# weblight_developer.net
KiCad netlist of a schematic drawn in EAGLE
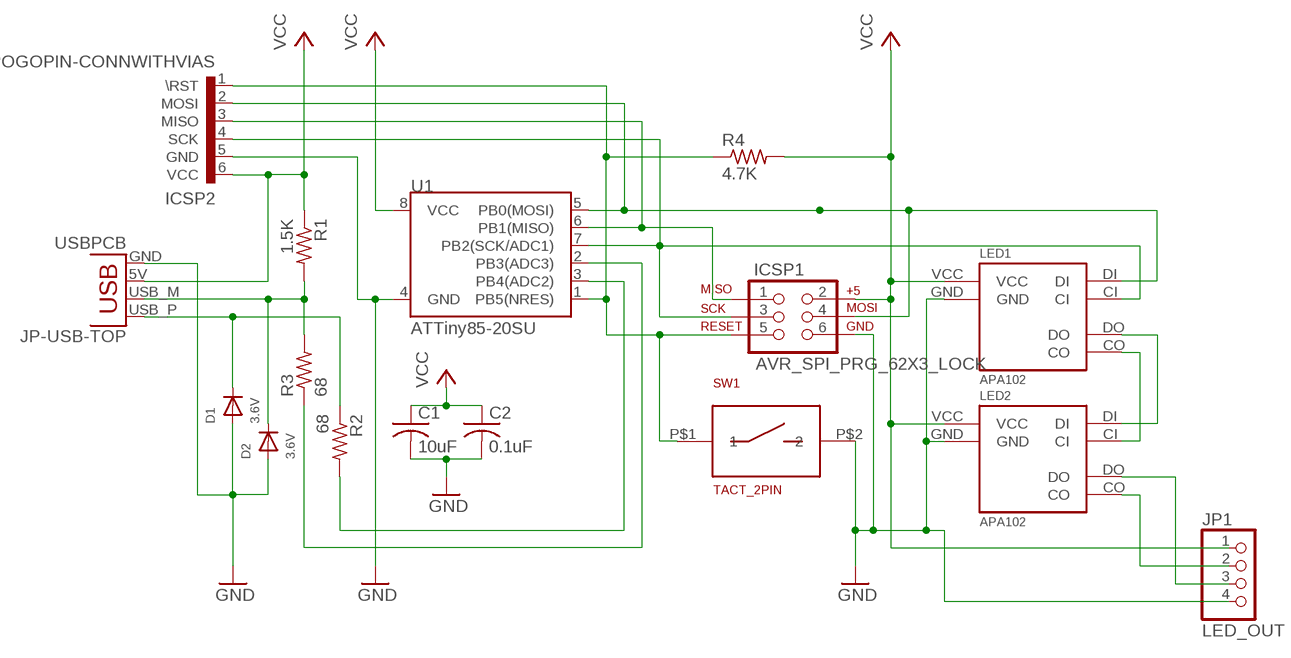
[diagram p0: schematic, sheet 1]

(export (version "E")
  (design (tool "Eeschema 10.0.6"))
  (components
    (comp (ref "C1")
      (value "10uF")
      (footprint "eagle-import:C0805")
      (libsource (lib "eagle-import") (part "C-USC0805"))
    )
    (comp (ref "C2")
      (value "0.1uF")
      (footprint "eagle-import:C0805")
      (libsource (lib "eagle-import") (part "C-USC0805"))
    )
    (comp (ref "D1")
      (value "3.6V")
      (footprint "eagle-import:SOD-323")
      (libsource (lib "eagle-import") (part "DIODESOD-323"))
    )
    (comp (ref "D2")
      (value "3.6V")
      (footprint "eagle-import:SOD-323")
      (libsource (lib "eagle-import") (part "DIODESOD-323"))
    )
    (comp (ref "ICSP1")
      (value "AVR_SPI_PRG_62X3_LOCK")
      (footprint "eagle-import:2X3_LOCK")
      (libsource (lib "eagle-import") (part "AVR_SPI_PRG_62X3_LOCK"))
    )
    (comp (ref "ICSP2")
      (value "POGOPIN-CONNWITHVIAS")
      (footprint "eagle-import:POGOPROG-CONN-0H")
      (libsource (lib "eagle-import") (part "POGOPIN-CONNWITHVIAS"))
    )
    (comp (ref "JP-USB-TOP")
      (value "USBPCB")
      (footprint "eagle-import:USB-A-PCB")
      (libsource (lib "eagle-import") (part "USBPCB"))
    )
    (comp (ref "JP1")
      (value "LED_OUT")
      (footprint "eagle-import:1X04_ROUND")
      (libsource (lib "eagle-import") (part "HEADER-1X4ROUND"))
    )
    (comp (ref "LED1")
      (value "APA102")
      (footprint "eagle-import:APA102")
      (libsource (lib "eagle-import") (part "APA102"))
    )
    (comp (ref "LED2")
      (value "APA102")
      (footprint "eagle-import:APA102")
      (libsource (lib "eagle-import") (part "APA102"))
    )
    (comp (ref "R1")
      (value "1.5K")
      (footprint "eagle-import:R0805")
      (libsource (lib "eagle-import") (part "R-US_R0805"))
    )
    (comp (ref "R2")
      (value "68")
      (footprint "eagle-import:R0805")
      (libsource (lib "eagle-import") (part "R-US_R0805"))
    )
    (comp (ref "R3")
      (value "68")
      (footprint "eagle-import:R0805")
      (libsource (lib "eagle-import") (part "R-US_R0805"))
    )
    (comp (ref "R4")
      (value "4.7K")
      (footprint "eagle-import:R0805")
      (libsource (lib "eagle-import") (part "R-US_R0805"))
    )
    (comp (ref "SW1")
      (value "TACT_2PIN")
      (footprint "eagle-import:TD-85XU")
      (libsource (lib "eagle-import") (part "TACT_2PIN"))
    )
    (comp (ref "U1")
      (value "ATTiny85-20SU")
      (footprint "eagle-import:SO08-EIAJ")
      (libsource (lib "eagle-import") (part "ATTINY45TINY85-20-SMT"))
    )
  )
  (nets
    (net (code "1") (name "GND") (class "Default")
      (node (ref "C1") (pin "2") (pinfunction "2_2") (pintype "passive"))
      (node (ref "C2") (pin "2") (pinfunction "2_2") (pintype "passive"))
      (node (ref "D1") (pin "A") (pinfunction "A_A") (pintype "passive"))
      (node (ref "D2") (pin "A") (pinfunction "A_A") (pintype "passive"))
      (node (ref "ICSP1") (pin "6") (pinfunction "6_6") (pintype "passive"))
      (node (ref "ICSP2") (pin "5") (pinfunction "GND_5") (pintype "bidirectional"))
      (node (ref "JP-USB-TOP") (pin "GND") (pinfunction "GND_GND") (pintype "bidirectional"))
      (node (ref "JP1") (pin "4") (pinfunction "4_4") (pintype "passive"))
      (node (ref "LED1") (pin "GND") (pinfunction "GND_GND") (pintype "power_in"))
      (node (ref "LED2") (pin "GND") (pinfunction "GND_GND") (pintype "power_in"))
      (node (ref "SW1") (pin "P$2") (pinfunction "2_P$2") (pintype "bidirectional"))
      (node (ref "U1") (pin "4") (pinfunction "GND_4") (pintype "bidirectional"))
    )
    (net (code "2") (name "Net-(ICSP2-MISO)") (class "Default")
      (node (ref "ICSP1") (pin "1") (pinfunction "1_1") (pintype "passive"))
      (node (ref "ICSP2") (pin "3") (pinfunction "MISO_3") (pintype "bidirectional"))
      (node (ref "U1") (pin "6") (pinfunction "PB1(MISO)_6") (pintype "bidirectional"))
    )
    (net (code "3") (name "Net-(ICSP2-MOSI)") (class "Default")
      (node (ref "ICSP1") (pin "4") (pinfunction "4_4") (pintype "passive"))
      (node (ref "ICSP2") (pin "2") (pinfunction "MOSI_2") (pintype "bidirectional"))
      (node (ref "LED1") (pin "DI") (pinfunction "DI_DI") (pintype "input"))
      (node (ref "U1") (pin "5") (pinfunction "PB0(MOSI)_5") (pintype "bidirectional"))
    )
    (net (code "4") (name "Net-(ICSP2-SCK)") (class "Default")
      (node (ref "ICSP1") (pin "3") (pinfunction "3_3") (pintype "passive"))
      (node (ref "ICSP2") (pin "4") (pinfunction "SCK_4") (pintype "bidirectional"))
      (node (ref "LED1") (pin "CI") (pinfunction "CI_CI") (pintype "input"))
      (node (ref "U1") (pin "7") (pinfunction "PB2(SCK/ADC1)_7") (pintype "bidirectional"))
    )
    (net (code "5") (name "Net-(ICSP2-\\RST)") (class "Default")
      (node (ref "ICSP1") (pin "5") (pinfunction "5_5") (pintype "passive"))
      (node (ref "ICSP2") (pin "1") (pinfunction "\\RST_1") (pintype "bidirectional"))
      (node (ref "R4") (pin "1") (pinfunction "1_1") (pintype "passive"))
      (node (ref "SW1") (pin "P$1") (pinfunction "1_P$1") (pintype "bidirectional"))
      (node (ref "U1") (pin "1") (pinfunction "PB5(NRES)_1") (pintype "bidirectional"))
    )
    (net (code "6") (name "Net-(JP-USB-TOP-D+)") (class "Default")
      (node (ref "D1") (pin "C") (pinfunction "C_C") (pintype "passive"))
      (node (ref "JP-USB-TOP") (pin "USB_P") (pinfunction "D+_USB_P") (pintype "bidirectional"))
      (node (ref "R2") (pin "1") (pinfunction "1_1") (pintype "passive"))
    )
    (net (code "7") (name "Net-(JP-USB-TOP-D-)") (class "Default")
      (node (ref "D2") (pin "C") (pinfunction "C_C") (pintype "passive"))
      (node (ref "JP-USB-TOP") (pin "USB_M") (pinfunction "D-_USB_M") (pintype "bidirectional"))
      (node (ref "R1") (pin "2") (pinfunction "2_2") (pintype "passive"))
      (node (ref "R3") (pin "2") (pinfunction "2_2") (pintype "passive"))
    )
    (net (code "8") (name "Net-(JP1-Pad2)") (class "Default")
      (node (ref "JP1") (pin "2") (pinfunction "2_2") (pintype "passive"))
      (node (ref "LED2") (pin "CO") (pinfunction "CO_CO") (pintype "output"))
    )
    (net (code "9") (name "Net-(JP1-Pad3)") (class "Default")
      (node (ref "JP1") (pin "3") (pinfunction "3_3") (pintype "passive"))
      (node (ref "LED2") (pin "DO") (pinfunction "DO_DO") (pintype "output"))
    )
    (net (code "10") (name "Net-(LED1-PadCO)") (class "Default")
      (node (ref "LED1") (pin "CO") (pinfunction "CO_CO") (pintype "output"))
      (node (ref "LED2") (pin "CI") (pinfunction "CI_CI") (pintype "input"))
    )
    (net (code "11") (name "Net-(LED1-PadDO)") (class "Default")
      (node (ref "LED1") (pin "DO") (pinfunction "DO_DO") (pintype "output"))
      (node (ref "LED2") (pin "DI") (pinfunction "DI_DI") (pintype "input"))
    )
    (net (code "12") (name "Net-(U1-PB3(ADC3))") (class "Default")
      (node (ref "R3") (pin "1") (pinfunction "1_1") (pintype "passive"))
      (node (ref "U1") (pin "2") (pinfunction "PB3(ADC3)_2") (pintype "bidirectional"))
    )
    (net (code "13") (name "Net-(U1-PB4(ADC2))") (class "Default")
      (node (ref "R2") (pin "2") (pinfunction "2_2") (pintype "passive"))
      (node (ref "U1") (pin "3") (pinfunction "PB4(ADC2)_3") (pintype "bidirectional"))
    )
    (net (code "14") (name "VCC") (class "Default")
      (node (ref "C1") (pin "1") (pinfunction "1_1") (pintype "passive"))
      (node (ref "C2") (pin "1") (pinfunction "1_1") (pintype "passive"))
      (node (ref "ICSP1") (pin "2") (pinfunction "2_2") (pintype "passive"))
      (node (ref "ICSP2") (pin "6") (pinfunction "VCC_6") (pintype "bidirectional"))
      (node (ref "JP-USB-TOP") (pin "5V") (pinfunction "VBUS_5V") (pintype "bidirectional"))
      (node (ref "JP1") (pin "1") (pinfunction "1_1") (pintype "passive"))
      (node (ref "LED1") (pin "VCC") (pinfunction "VCC_VCC") (pintype "power_in"))
      (node (ref "LED2") (pin "VCC") (pinfunction "VCC_VCC") (pintype "power_in"))
      (node (ref "R1") (pin "1") (pinfunction "1_1") (pintype "passive"))
      (node (ref "R4") (pin "2") (pinfunction "2_2") (pintype "passive"))
      (node (ref "U1") (pin "8") (pinfunction "VCC_8") (pintype "bidirectional"))
    )
  )
)
